# Sheet.net
KiCad netlist of a schematic drawn in Altium Designer
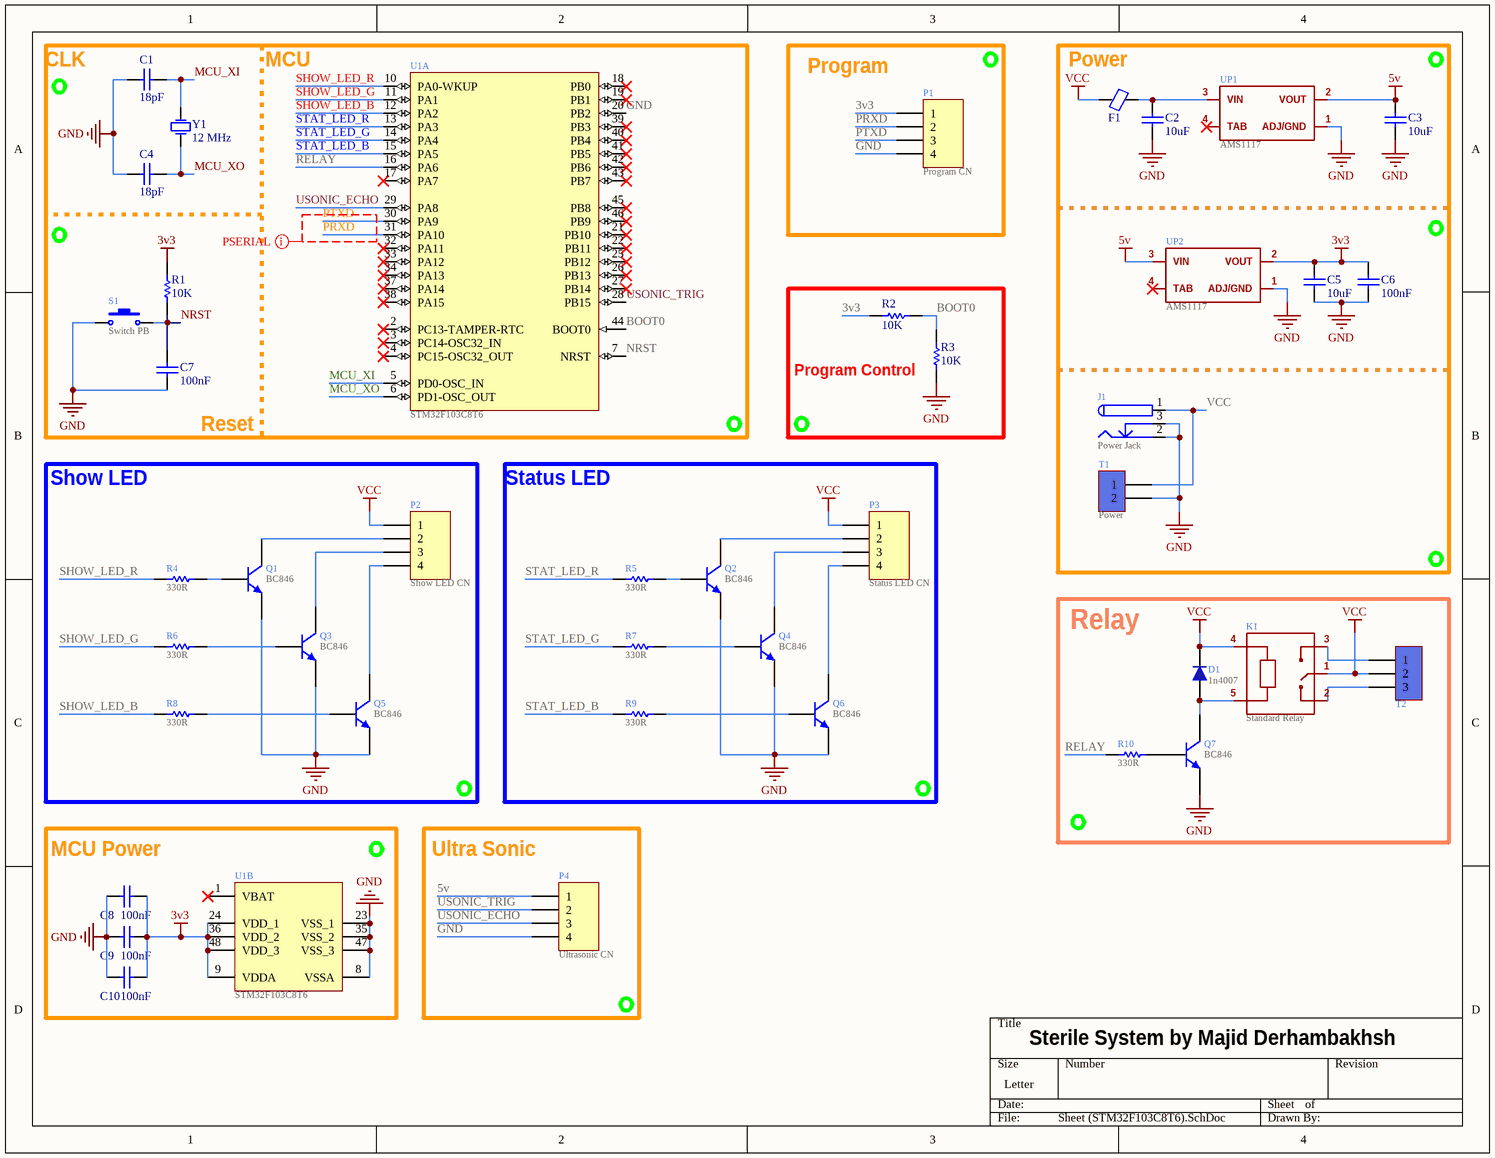
[diagram p0: Sheet (STM32F103C8T6).SchDoc]

(export (version "E")
  (design (tool "Eeschema 10.0.6"))
  (components
    (comp (ref "C1")
      (value "18pF")
      (footprint "CAP805")
      (description "TOTAL CAPACITOR SMD PACK")
      (fields (field (name "DESIGNER") "Majid Derhambakhsh"))
      (libsource (lib "Altium") (part "CAP SMD PACKAGE"))
    )
    (comp (ref "C2")
      (value "10uF")
      (footprint "Cap1206_(3216X15)")
      (description "TOTAL CAPACITOR SMD PACK")
      (fields (field (name "DESIGNER") "Abbas Basereh"))
      (libsource (lib "Altium") (part "CAP SMD PACKAGE"))
    )
    (comp (ref "C3")
      (value "10uF")
      (footprint "Cap1206_(3216X15)")
      (description "TOTAL CAPACITOR SMD PACK")
      (fields (field (name "DESIGNER") "Abbas Basereh"))
      (libsource (lib "Altium") (part "CAP SMD PACKAGE"))
    )
    (comp (ref "C4")
      (value "18pF")
      (footprint "CAP805")
      (description "TOTAL CAPACITOR SMD PACK")
      (fields (field (name "DESIGNER") "Majid Derhambakhsh"))
      (libsource (lib "Altium") (part "CAP SMD PACKAGE"))
    )
    (comp (ref "C5")
      (value "10uF")
      (footprint "Cap1206_(3216X15)")
      (description "TOTAL CAPACITOR SMD PACK")
      (fields (field (name "DESIGNER") "Abbas Basereh"))
      (libsource (lib "Altium") (part "CAP SMD PACKAGE"))
    )
    (comp (ref "C6")
      (value "100nF")
      (footprint "Cap1206_(3216X15)")
      (description "TOTAL CAPACITOR SMD PACK")
      (fields (field (name "DESIGNER") "Majid Derhambakhsh"))
      (libsource (lib "Altium") (part "CAP SMD PACKAGE"))
    )
    (comp (ref "C7")
      (value "100nF")
      (footprint "Cap1206_(3216X15L)")
      (description "TOTAL CAPACITOR SMD PACK")
      (fields (field (name "DESIGNER") "Majid Derhambakhsh"))
      (libsource (lib "Altium") (part "CAP SMD PACKAGE"))
    )
    (comp (ref "C8")
      (value "100nF")
      (footprint "Cap1206_(3216X15L)")
      (description "TOTAL CAPACITOR SMD PACK")
      (fields (field (name "DESIGNER") "Majid Derhambakhsh"))
      (libsource (lib "Altium") (part "CAP SMD PACKAGE"))
    )
    (comp (ref "C9")
      (value "100nF")
      (footprint "Cap1206_(3216X15L)")
      (description "TOTAL CAPACITOR SMD PACK")
      (fields (field (name "DESIGNER") "Majid Derhambakhsh"))
      (libsource (lib "Altium") (part "CAP SMD PACKAGE"))
    )
    (comp (ref "C10")
      (value "100nF")
      (footprint "Cap1206_(3216X15L)")
      (description "TOTAL CAPACITOR SMD PACK")
      (fields (field (name "DESIGNER") "Majid Derhambakhsh"))
      (libsource (lib "Altium") (part "CAP SMD PACKAGE"))
    )
    (comp (ref "D1")
      (value "1n4007")
      (footprint "DIOM4629X24N")
      (description "Standard Rectifiers")
      (fields (field (name "MANUFACTURER") "DC COMPONENTS") (field (name "DESIGNER") "Abbas Basereh"))
      (libsource (lib "Altium") (part "1n4007 SMD M7"))
    )
    (comp (ref "F1")
      (value "Ferrite Bead SMD")
      (footprint "FB1206")
      (fields (field (name "DESIGNER") "Ali Hafizi"))
      (libsource (lib "Altium") (part "Ferrite Bead SMD Package"))
    )
    (comp (ref "J1")
      (value "Power Jack")
      (footprint "DC Power Jack")
      (fields (field (name "DESIGNER") "Majid Derhambakhsh"))
      (libsource (lib "Altium library") (part "DC Power Jack"))
    )
    (comp (ref "K1")
      (value "Standard Relay")
      (footprint "BABY Milon Relay (15.40x12.10x13.10)")
      (description "Relay SPDT POWER NEEDLE")
      (fields (field (name "DESIGNER") "Ali Hafizi"))
      (libsource (lib "Altium library") (part "Relay"))
    )
    (comp (ref "P1")
      (value "Program CN")
      (footprint "HDR1X4")
      (description "Header, 4-Pin")
      (fields (field (name "PUBLISHER") "Altium Limited"))
      (libsource (lib "Miscellaneous Connectors") (part "Header 4"))
    )
    (comp (ref "P2")
      (value "Show LED CN")
      (footprint "HDR1X4")
      (description "Header, 4-Pin")
      (fields (field (name "PUBLISHER") "Altium Limited"))
      (libsource (lib "Miscellaneous Connectors") (part "Header 4"))
    )
    (comp (ref "P3")
      (value "Status LED CN")
      (footprint "HDR1X4")
      (description "Header, 4-Pin")
      (fields (field (name "PUBLISHER") "Altium Limited"))
      (libsource (lib "Miscellaneous Connectors") (part "Header 4"))
    )
    (comp (ref "P4")
      (value "Ultrasonic CN")
      (footprint "HDR1X4")
      (description "Header, 4-Pin")
      (fields (field (name "PUBLISHER") "Altium Limited"))
      (libsource (lib "Miscellaneous Connectors") (part "Header 4"))
    )
    (comp (ref "Q1")
      (value "BC846")
      (footprint "SOT23_L")
      (description "NPN General-purpose Transistor")
      (fields (field (name "PUBLISHER") "Abbas Basereh"))
      (libsource (lib "Altium") (part "BC846"))
    )
    (comp (ref "Q2")
      (value "BC846")
      (footprint "SOT23_L")
      (description "NPN General-purpose Transistor")
      (fields (field (name "PUBLISHER") "Abbas Basereh"))
      (libsource (lib "Altium") (part "BC846"))
    )
    (comp (ref "Q3")
      (value "BC846")
      (footprint "SOT23_L")
      (description "NPN General-purpose Transistor")
      (fields (field (name "PUBLISHER") "Abbas Basereh"))
      (libsource (lib "Altium") (part "BC846"))
    )
    (comp (ref "Q4")
      (value "BC846")
      (footprint "SOT23_L")
      (description "NPN General-purpose Transistor")
      (fields (field (name "PUBLISHER") "Abbas Basereh"))
      (libsource (lib "Altium") (part "BC846"))
    )
    (comp (ref "Q5")
      (value "BC846")
      (footprint "SOT23_L")
      (description "NPN General-purpose Transistor")
      (fields (field (name "PUBLISHER") "Abbas Basereh"))
      (libsource (lib "Altium") (part "BC846"))
    )
    (comp (ref "Q6")
      (value "BC846")
      (footprint "SOT23_L")
      (description "NPN General-purpose Transistor")
      (fields (field (name "PUBLISHER") "Abbas Basereh"))
      (libsource (lib "Altium") (part "BC846"))
    )
    (comp (ref "Q7")
      (value "BC846")
      (footprint "SOT23_L")
      (description "NPN General-purpose Transistor")
      (fields (field (name "PUBLISHER") "Abbas Basereh"))
      (libsource (lib "Altium") (part "BC846"))
    )
    (comp (ref "R1")
      (value "10K")
      (footprint "RES1206 _(3216X08L)")
      (description "TOTAL SMD RESISTOR PACK")
      (fields (field (name "DESIGNER") "Abbas Basereh"))
      (libsource (lib "Altium") (part "RES SMD PACKAGE"))
    )
    (comp (ref "R2")
      (value "10K")
      (footprint "RES1206 _(3216X08L)")
      (description "TOTAL SMD RESISTOR PACK")
      (fields (field (name "DESIGNER") "Abbas Basereh"))
      (libsource (lib "Altium") (part "RES SMD PACKAGE"))
    )
    (comp (ref "R3")
      (value "10K")
      (footprint "RES1206 _(3216X08L)")
      (description "TOTAL SMD RESISTOR PACK")
      (fields (field (name "DESIGNER") "Abbas Basereh"))
      (libsource (lib "Altium") (part "RES SMD PACKAGE"))
    )
    (comp (ref "R4")
      (value "330R")
      (footprint "RES1206 _(3216X08L)")
      (description "TOTAL SMD RESISTOR PACK")
      (fields (field (name "DESIGNER") "Abbas Basereh"))
      (libsource (lib "Altium") (part "RES SMD PACKAGE"))
    )
    (comp (ref "R5")
      (value "330R")
      (footprint "RES1206 _(3216X08L)")
      (description "TOTAL SMD RESISTOR PACK")
      (fields (field (name "DESIGNER") "Abbas Basereh"))
      (libsource (lib "Altium") (part "RES SMD PACKAGE"))
    )
    (comp (ref "R6")
      (value "330R")
      (footprint "RES1206 _(3216X08L)")
      (description "TOTAL SMD RESISTOR PACK")
      (fields (field (name "DESIGNER") "Abbas Basereh"))
      (libsource (lib "Altium") (part "RES SMD PACKAGE"))
    )
    (comp (ref "R7")
      (value "330R")
      (footprint "RES1206 _(3216X08L)")
      (description "TOTAL SMD RESISTOR PACK")
      (fields (field (name "DESIGNER") "Abbas Basereh"))
      (libsource (lib "Altium") (part "RES SMD PACKAGE"))
    )
    (comp (ref "R8")
      (value "330R")
      (footprint "RES1206 _(3216X08L)")
      (description "TOTAL SMD RESISTOR PACK")
      (fields (field (name "DESIGNER") "Abbas Basereh"))
      (libsource (lib "Altium") (part "RES SMD PACKAGE"))
    )
    (comp (ref "R9")
      (value "330R")
      (footprint "RES1206 _(3216X08L)")
      (description "TOTAL SMD RESISTOR PACK")
      (fields (field (name "DESIGNER") "Abbas Basereh"))
      (libsource (lib "Altium") (part "RES SMD PACKAGE"))
    )
    (comp (ref "R10")
      (value "330R")
      (footprint "RES1206 _(3216X08L)")
      (description "TOTAL SMD RESISTOR PACK")
      (fields (field (name "DESIGNER") "Abbas Basereh"))
      (libsource (lib "Altium") (part "RES SMD PACKAGE"))
    )
    (comp (ref "S1")
      (value "Switch PB")
      (footprint "Switch - Push to On")
      (description "Push Button Switch")
      (libsource (lib "Altium") (part "Switch PB"))
    )
    (comp (ref "T1")
      (value "Power")
      (footprint "KF301 2PIN")
      (description "Terminal 2 Pin 250VAC 16A")
      (fields (field (name "DESIGNER") "Abbas Basereh"))
      (libsource (lib "Altium") (part "KF301-2Pin_Terminal"))
    )
    (comp (ref "T2")
      (value "KF301_Terminal")
      (footprint "KF301 3PIN")
      (description "Terminal 3 Pin 250VAC 16A")
      (fields (field (name "DESIGNER") "Abbas Basereh"))
      (libsource (lib "Altium") (part "KF301-3Pin_Terminal"))
    )
    (comp (ref "U1")
      (value "STM32F103C8T6")
      (footprint "STM-LQFP48_M")
      (libsource (lib "STMicroelectronics STM32 F1") (part "STM32F103C8T6"))
    )
    (comp (ref "UP1")
      (value "AMS1117")
      (footprint "SOT223")
      (description "x.x Volt, 800mA Low-Dropout Linear Regulator, 4-pin SOT-223")
      (fields (field (name "DESIGNER") "Ali Hafizi"))
      (libsource (lib "Altium library") (part "AMS1117"))
    )
    (comp (ref "UP2")
      (value "AMS1117")
      (footprint "SOT223")
      (description "x.x Volt, 800mA Low-Dropout Linear Regulator, 4-pin SOT-223")
      (fields (field (name "DESIGNER") "Ali Hafizi"))
      (libsource (lib "Altium library") (part "AMS1117"))
    )
    (comp (ref "Y1")
      (value "12 MHz")
      (footprint "XTAL 16MHZ")
      (description "XTAL Crystal")
      (fields (field (name "DESIGNER") "ABBAS BASEREH"))
      (libsource (lib "Altium") (part "XTAL"))
    )
  )
  (nets
    (net (code "1") (name "/BOOT0") (class "Default")
      (node (ref "R2") (pin "1") (pinfunction "1_1") (pintype "passive"))
      (node (ref "R3") (pin "2") (pinfunction "2_2") (pintype "passive"))
      (node (ref "U1") (pin "44") (pinfunction "BOOT0_44") (pintype "input"))
    )
    (net (code "2") (name "/MCU_XI") (class "Default")
      (node (ref "C1") (pin "1") (pinfunction "1_1") (pintype "passive"))
      (node (ref "U1") (pin "5") (pinfunction "PD0-OSC_IN_5") (pintype "bidirectional"))
      (node (ref "Y1") (pin "2") (pinfunction "OSC2_2") (pintype "passive"))
    )
    (net (code "3") (name "/MCU_XO") (class "Default")
      (node (ref "C4") (pin "1") (pinfunction "1_1") (pintype "passive"))
      (node (ref "U1") (pin "6") (pinfunction "PD1-OSC_OUT_6") (pintype "bidirectional"))
      (node (ref "Y1") (pin "1") (pinfunction "OSC1_1") (pintype "passive"))
    )
    (net (code "4") (name "/NRST") (class "Default")
      (node (ref "C7") (pin "2") (pinfunction "2_2") (pintype "passive"))
      (node (ref "R1") (pin "1") (pinfunction "1_1") (pintype "passive"))
      (node (ref "S1") (pin "2") (pinfunction "2_2") (pintype "passive"))
      (node (ref "U1") (pin "7") (pinfunction "NRST_7") (pintype "bidirectional"))
    )
    (net (code "5") (name "/PRXD") (class "Default")
      (node (ref "P1") (pin "2") (pinfunction "2_2") (pintype "passive"))
      (node (ref "U1") (pin "31") (pinfunction "PA10_31") (pintype "bidirectional"))
    )
    (net (code "6") (name "/PTXD") (class "Default")
      (node (ref "P1") (pin "3") (pinfunction "3_3") (pintype "passive"))
      (node (ref "U1") (pin "30") (pinfunction "PA9_30") (pintype "bidirectional"))
    )
    (net (code "7") (name "/RELAY") (class "Default")
      (node (ref "R10") (pin "1") (pinfunction "1_1") (pintype "passive"))
      (node (ref "U1") (pin "16") (pinfunction "PA6_16") (pintype "bidirectional"))
    )
    (net (code "8") (name "/SHOW_LED_B") (class "Default")
      (node (ref "R8") (pin "1") (pinfunction "1_1") (pintype "passive"))
      (node (ref "U1") (pin "12") (pinfunction "PA2_12") (pintype "bidirectional"))
    )
    (net (code "9") (name "/SHOW_LED_G") (class "Default")
      (node (ref "R6") (pin "1") (pinfunction "1_1") (pintype "passive"))
      (node (ref "U1") (pin "11") (pinfunction "PA1_11") (pintype "bidirectional"))
    )
    (net (code "10") (name "/SHOW_LED_R") (class "Default")
      (node (ref "R4") (pin "1") (pinfunction "1_1") (pintype "passive"))
      (node (ref "U1") (pin "10") (pinfunction "PA0-WKUP_10") (pintype "bidirectional"))
    )
    (net (code "11") (name "/STAT_LED_B") (class "Default")
      (node (ref "R9") (pin "1") (pinfunction "1_1") (pintype "passive"))
      (node (ref "U1") (pin "15") (pinfunction "PA5_15") (pintype "bidirectional"))
    )
    (net (code "12") (name "/STAT_LED_G") (class "Default")
      (node (ref "R7") (pin "1") (pinfunction "1_1") (pintype "passive"))
      (node (ref "U1") (pin "14") (pinfunction "PA4_14") (pintype "bidirectional"))
    )
    (net (code "13") (name "/STAT_LED_R") (class "Default")
      (node (ref "R5") (pin "1") (pinfunction "1_1") (pintype "passive"))
      (node (ref "U1") (pin "13") (pinfunction "PA3_13") (pintype "bidirectional"))
    )
    (net (code "14") (name "/USONIC_ECHO") (class "Default")
      (node (ref "P4") (pin "3") (pinfunction "3_3") (pintype "passive"))
      (node (ref "U1") (pin "29") (pinfunction "PA8_29") (pintype "bidirectional"))
    )
    (net (code "15") (name "/USONIC_TRIG") (class "Default")
      (node (ref "P4") (pin "2") (pinfunction "2_2") (pintype "passive"))
      (node (ref "U1") (pin "28") (pinfunction "PB15_28") (pintype "bidirectional"))
    )
    (net (code "16") (name "3v3") (class "Default")
      (node (ref "C10") (pin "2") (pinfunction "2_2") (pintype "passive"))
      (node (ref "C5") (pin "2") (pinfunction "2_2") (pintype "passive"))
      (node (ref "C6") (pin "2") (pinfunction "2_2") (pintype "passive"))
      (node (ref "C8") (pin "2") (pinfunction "2_2") (pintype "passive"))
      (node (ref "C9") (pin "2") (pinfunction "2_2") (pintype "passive"))
      (node (ref "P1") (pin "1") (pinfunction "1_1") (pintype "passive"))
      (node (ref "R1") (pin "2") (pinfunction "2_2") (pintype "passive"))
      (node (ref "R2") (pin "2") (pinfunction "2_2") (pintype "passive"))
      (node (ref "U1") (pin "24") (pinfunction "VDD_1_24") (pintype "power_in"))
      (node (ref "U1") (pin "36") (pinfunction "VDD_2_36") (pintype "power_in"))
      (node (ref "U1") (pin "48") (pinfunction "VDD_3_48") (pintype "power_in"))
      (node (ref "U1") (pin "9") (pinfunction "VDDA_9") (pintype "power_in"))
      (node (ref "UP2") (pin "2") (pinfunction "VOUT_2") (pintype "open_collector"))
    )
    (net (code "17") (name "5v") (class "Default")
      (node (ref "C3") (pin "2") (pinfunction "2_2") (pintype "passive"))
      (node (ref "P4") (pin "1") (pinfunction "1_1") (pintype "passive"))
      (node (ref "UP1") (pin "2") (pinfunction "VOUT_2") (pintype "open_collector"))
      (node (ref "UP2") (pin "3") (pinfunction "VIN_3") (pintype "open_collector"))
    )
    (net (code "18") (name "GND") (class "Default")
      (node (ref "C1") (pin "2") (pinfunction "2_2") (pintype "passive"))
      (node (ref "C10") (pin "1") (pinfunction "1_1") (pintype "passive"))
      (node (ref "C2") (pin "1") (pinfunction "1_1") (pintype "passive"))
      (node (ref "C3") (pin "1") (pinfunction "1_1") (pintype "passive"))
      (node (ref "C4") (pin "2") (pinfunction "2_2") (pintype "passive"))
      (node (ref "C5") (pin "1") (pinfunction "1_1") (pintype "passive"))
      (node (ref "C6") (pin "1") (pinfunction "1_1") (pintype "passive"))
      (node (ref "C7") (pin "1") (pinfunction "1_1") (pintype "passive"))
      (node (ref "C8") (pin "1") (pinfunction "1_1") (pintype "passive"))
      (node (ref "C9") (pin "1") (pinfunction "1_1") (pintype "passive"))
      (node (ref "J1") (pin "2") (pinfunction "2_2") (pintype "power_in"))
      (node (ref "J1") (pin "3") (pinfunction "3_3") (pintype "power_in"))
      (node (ref "P1") (pin "4") (pinfunction "4_4") (pintype "passive"))
      (node (ref "P4") (pin "4") (pinfunction "4_4") (pintype "passive"))
      (node (ref "Q1") (pin "2") (pinfunction "E_2") (pintype "passive"))
      (node (ref "Q2") (pin "2") (pinfunction "E_2") (pintype "passive"))
      (node (ref "Q3") (pin "2") (pinfunction "E_2") (pintype "passive"))
      (node (ref "Q4") (pin "2") (pinfunction "E_2") (pintype "passive"))
      (node (ref "Q5") (pin "2") (pinfunction "E_2") (pintype "passive"))
      (node (ref "Q6") (pin "2") (pinfunction "E_2") (pintype "passive"))
      (node (ref "Q7") (pin "2") (pinfunction "E_2") (pintype "passive"))
      (node (ref "R3") (pin "1") (pinfunction "1_1") (pintype "passive"))
      (node (ref "S1") (pin "1") (pinfunction "1_1") (pintype "passive"))
      (node (ref "T1") (pin "2") (pinfunction "2_2") (pintype "passive"))
      (node (ref "U1") (pin "20") (pinfunction "PB2_20") (pintype "bidirectional"))
      (node (ref "U1") (pin "23") (pinfunction "VSS_1_23") (pintype "power_in"))
      (node (ref "U1") (pin "35") (pinfunction "VSS_2_35") (pintype "power_in"))
      (node (ref "U1") (pin "47") (pinfunction "VSS_3_47") (pintype "power_in"))
      (node (ref "U1") (pin "8") (pinfunction "VSSA_8") (pintype "power_in"))
      (node (ref "UP1") (pin "1") (pinfunction "ADJ/GND_1") (pintype "open_collector"))
      (node (ref "UP2") (pin "1") (pinfunction "ADJ/GND_1") (pintype "open_collector"))
    )
    (net (code "19") (name "Net-(K1-N.C)") (class "Default")
      (node (ref "K1") (pin "2") (pinfunction "N.C_2") (pintype "open_collector"))
      (node (ref "T2") (pin "3") (pinfunction "3_3") (pintype "passive"))
    )
    (net (code "20") (name "Net-(K1-N.O)") (class "Default")
      (node (ref "K1") (pin "3") (pinfunction "N.O_3") (pintype "open_collector"))
      (node (ref "T2") (pin "1") (pinfunction "1_1") (pintype "passive"))
    )
    (net (code "21") (name "Net-(Q1-B)") (class "Default")
      (node (ref "Q1") (pin "1") (pinfunction "B_1") (pintype "passive"))
      (node (ref "R4") (pin "2") (pinfunction "2_2") (pintype "passive"))
    )
    (net (code "22") (name "Net-(Q1-C)") (class "Default")
      (node (ref "P2") (pin "2") (pinfunction "2_2") (pintype "passive"))
      (node (ref "Q1") (pin "3") (pinfunction "C_3") (pintype "passive"))
    )
    (net (code "23") (name "Net-(Q2-B)") (class "Default")
      (node (ref "Q2") (pin "1") (pinfunction "B_1") (pintype "passive"))
      (node (ref "R5") (pin "2") (pinfunction "2_2") (pintype "passive"))
    )
    (net (code "24") (name "Net-(Q2-C)") (class "Default")
      (node (ref "P3") (pin "2") (pinfunction "2_2") (pintype "passive"))
      (node (ref "Q2") (pin "3") (pinfunction "C_3") (pintype "passive"))
    )
    (net (code "25") (name "Net-(Q3-B)") (class "Default")
      (node (ref "Q3") (pin "1") (pinfunction "B_1") (pintype "passive"))
      (node (ref "R6") (pin "2") (pinfunction "2_2") (pintype "passive"))
    )
    (net (code "26") (name "Net-(Q3-C)") (class "Default")
      (node (ref "P2") (pin "3") (pinfunction "3_3") (pintype "passive"))
      (node (ref "Q3") (pin "3") (pinfunction "C_3") (pintype "passive"))
    )
    (net (code "27") (name "Net-(Q4-B)") (class "Default")
      (node (ref "Q4") (pin "1") (pinfunction "B_1") (pintype "passive"))
      (node (ref "R7") (pin "2") (pinfunction "2_2") (pintype "passive"))
    )
    (net (code "28") (name "Net-(Q4-C)") (class "Default")
      (node (ref "P3") (pin "3") (pinfunction "3_3") (pintype "passive"))
      (node (ref "Q4") (pin "3") (pinfunction "C_3") (pintype "passive"))
    )
    (net (code "29") (name "Net-(Q5-B)") (class "Default")
      (node (ref "Q5") (pin "1") (pinfunction "B_1") (pintype "passive"))
      (node (ref "R8") (pin "2") (pinfunction "2_2") (pintype "passive"))
    )
    (net (code "30") (name "Net-(Q5-C)") (class "Default")
      (node (ref "P2") (pin "4") (pinfunction "4_4") (pintype "passive"))
      (node (ref "Q5") (pin "3") (pinfunction "C_3") (pintype "passive"))
    )
    (net (code "31") (name "Net-(Q6-B)") (class "Default")
      (node (ref "Q6") (pin "1") (pinfunction "B_1") (pintype "passive"))
      (node (ref "R9") (pin "2") (pinfunction "2_2") (pintype "passive"))
    )
    (net (code "32") (name "Net-(Q6-C)") (class "Default")
      (node (ref "P3") (pin "4") (pinfunction "4_4") (pintype "passive"))
      (node (ref "Q6") (pin "3") (pinfunction "C_3") (pintype "passive"))
    )
    (net (code "33") (name "Net-(Q7-B)") (class "Default")
      (node (ref "Q7") (pin "1") (pinfunction "B_1") (pintype "passive"))
      (node (ref "R10") (pin "2") (pinfunction "2_2") (pintype "passive"))
    )
    (net (code "34") (name "Net-(Q7-C)") (class "Default")
      (node (ref "D1") (pin "1") (pintype "passive"))
      (node (ref "K1") (pin "5") (pinfunction "A_5") (pintype "open_collector"))
      (node (ref "Q7") (pin "3") (pinfunction "C_3") (pintype "passive"))
    )
    (net (code "35") (name "Net-(UP1-VIN)") (class "Default")
      (node (ref "C2") (pin "2") (pinfunction "2_2") (pintype "passive"))
      (node (ref "F1") (pin "1") (pinfunction "1_1") (pintype "passive"))
      (node (ref "UP1") (pin "3") (pinfunction "VIN_3") (pintype "open_collector"))
    )
    (net (code "36") (name "VCC") (class "Default")
      (node (ref "D1") (pin "2") (pintype "passive"))
      (node (ref "F1") (pin "2") (pinfunction "2_2") (pintype "passive"))
      (node (ref "J1") (pin "1") (pinfunction "1_1") (pintype "power_in"))
      (node (ref "K1") (pin "1") (pinfunction "COM_1") (pintype "open_collector"))
      (node (ref "K1") (pin "4") (pinfunction "A_4") (pintype "open_collector"))
      (node (ref "P2") (pin "1") (pinfunction "1_1") (pintype "passive"))
      (node (ref "P3") (pin "1") (pinfunction "1_1") (pintype "passive"))
      (node (ref "T1") (pin "1") (pinfunction "1_1") (pintype "passive"))
      (node (ref "T2") (pin "2") (pinfunction "2_2") (pintype "passive"))
    )
    (net (code "37") (name "unconnected-(U1A-PA7-Pad17)") (class "Default")
      (node (ref "U1") (pin "17") (pinfunction "PA7_17") (pintype "bidirectional+no_connect"))
    )
    (net (code "38") (name "unconnected-(U1A-PA11-Pad32)") (class "Default")
      (node (ref "U1") (pin "32") (pinfunction "PA11_32") (pintype "bidirectional+no_connect"))
    )
    (net (code "39") (name "unconnected-(U1A-PA12-Pad33)") (class "Default")
      (node (ref "U1") (pin "33") (pinfunction "PA12_33") (pintype "bidirectional+no_connect"))
    )
    (net (code "40") (name "unconnected-(U1A-PA13-Pad34)") (class "Default")
      (node (ref "U1") (pin "34") (pinfunction "PA13_34") (pintype "bidirectional+no_connect"))
    )
    (net (code "41") (name "unconnected-(U1A-PA14-Pad37)") (class "Default")
      (node (ref "U1") (pin "37") (pinfunction "PA14_37") (pintype "bidirectional+no_connect"))
    )
    (net (code "42") (name "unconnected-(U1A-PA15-Pad38)") (class "Default")
      (node (ref "U1") (pin "38") (pinfunction "PA15_38") (pintype "bidirectional+no_connect"))
    )
    (net (code "43") (name "unconnected-(U1A-PB0-Pad18)") (class "Default")
      (node (ref "U1") (pin "18") (pinfunction "PB0_18") (pintype "bidirectional+no_connect"))
    )
    (net (code "44") (name "unconnected-(U1A-PB1-Pad19)") (class "Default")
      (node (ref "U1") (pin "19") (pinfunction "PB1_19") (pintype "bidirectional+no_connect"))
    )
    (net (code "45") (name "unconnected-(U1A-PB3-Pad39)") (class "Default")
      (node (ref "U1") (pin "39") (pinfunction "PB3_39") (pintype "bidirectional+no_connect"))
    )
    (net (code "46") (name "unconnected-(U1A-PB4-Pad40)") (class "Default")
      (node (ref "U1") (pin "40") (pinfunction "PB4_40") (pintype "bidirectional+no_connect"))
    )
    (net (code "47") (name "unconnected-(U1A-PB5-Pad41)") (class "Default")
      (node (ref "U1") (pin "41") (pinfunction "PB5_41") (pintype "bidirectional+no_connect"))
    )
    (net (code "48") (name "unconnected-(U1A-PB6-Pad42)") (class "Default")
      (node (ref "U1") (pin "42") (pinfunction "PB6_42") (pintype "bidirectional+no_connect"))
    )
    (net (code "49") (name "unconnected-(U1A-PB7-Pad43)") (class "Default")
      (node (ref "U1") (pin "43") (pinfunction "PB7_43") (pintype "bidirectional+no_connect"))
    )
    (net (code "50") (name "unconnected-(U1A-PB8-Pad45)") (class "Default")
      (node (ref "U1") (pin "45") (pinfunction "PB8_45") (pintype "bidirectional+no_connect"))
    )
    (net (code "51") (name "unconnected-(U1A-PB9-Pad46)") (class "Default")
      (node (ref "U1") (pin "46") (pinfunction "PB9_46") (pintype "bidirectional+no_connect"))
    )
    (net (code "52") (name "unconnected-(U1A-PB10-Pad21)") (class "Default")
      (node (ref "U1") (pin "21") (pinfunction "PB10_21") (pintype "bidirectional+no_connect"))
    )
    (net (code "53") (name "unconnected-(U1A-PB11-Pad22)") (class "Default")
      (node (ref "U1") (pin "22") (pinfunction "PB11_22") (pintype "bidirectional+no_connect"))
    )
    (net (code "54") (name "unconnected-(U1A-PB12-Pad25)") (class "Default")
      (node (ref "U1") (pin "25") (pinfunction "PB12_25") (pintype "bidirectional+no_connect"))
    )
    (net (code "55") (name "unconnected-(U1A-PB13-Pad26)") (class "Default")
      (node (ref "U1") (pin "26") (pinfunction "PB13_26") (pintype "bidirectional+no_connect"))
    )
    (net (code "56") (name "unconnected-(U1A-PB14-Pad27)") (class "Default")
      (node (ref "U1") (pin "27") (pinfunction "PB14_27") (pintype "bidirectional+no_connect"))
    )
    (net (code "57") (name "unconnected-(U1A-PC13-TAMPER-RTC-Pad2)") (class "Default")
      (node (ref "U1") (pin "2") (pinfunction "PC13-TAMPER-RTC_2") (pintype "bidirectional+no_connect"))
    )
    (net (code "58") (name "unconnected-(U1A-PC14-OSC32_IN-Pad3)") (class "Default")
      (node (ref "U1") (pin "3") (pinfunction "PC14-OSC32_IN_3") (pintype "bidirectional+no_connect"))
    )
    (net (code "59") (name "unconnected-(U1A-PC15-OSC32_OUT-Pad4)") (class "Default")
      (node (ref "U1") (pin "4") (pinfunction "PC15-OSC32_OUT_4") (pintype "bidirectional+no_connect"))
    )
    (net (code "60") (name "unconnected-(U1B-VBAT-Pad1)") (class "Default")
      (node (ref "U1") (pin "1") (pinfunction "VBAT_1") (pintype "power_in+no_connect"))
    )
    (net (code "61") (name "unconnected-(UP1-TAB-Pad4)") (class "Default")
      (node (ref "UP1") (pin "4") (pinfunction "TAB_4") (pintype "open_collector+no_connect"))
    )
    (net (code "62") (name "unconnected-(UP2-TAB-Pad4)") (class "Default")
      (node (ref "UP2") (pin "4") (pinfunction "TAB_4") (pintype "open_collector+no_connect"))
    )
  )
)
